# 8iSwitchesOK.net
KiCad netlist of a schematic drawn in EAGLE
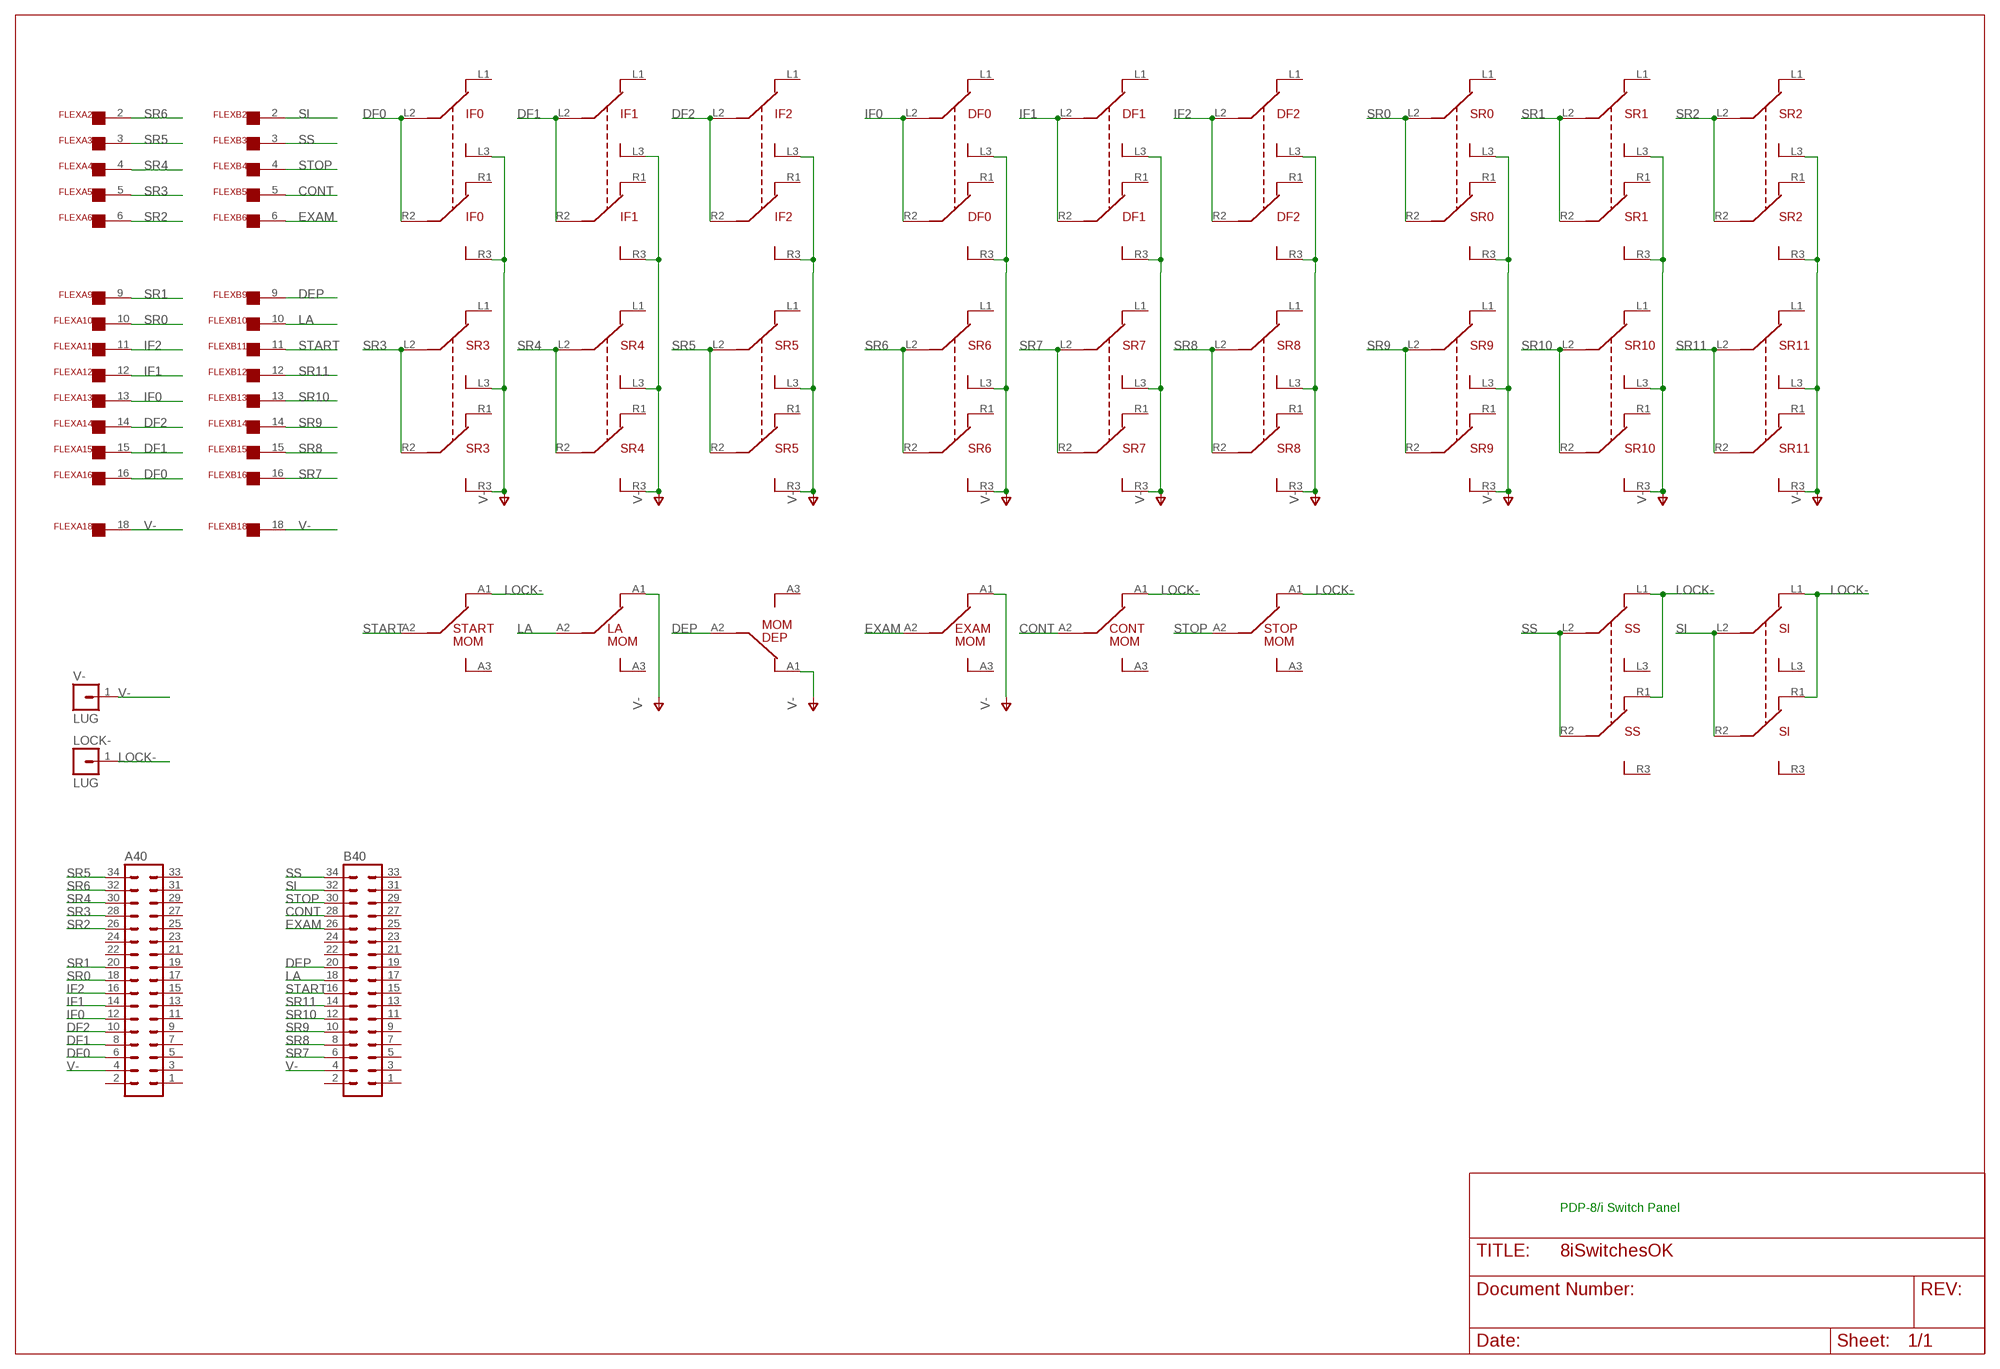
[diagram p0: schematic, sheet 1]

(export (version "E")
  (design (tool "Eeschema 10.0.6"))
  (components
    (comp (ref "A40")
      (value "MA17-2")
      (footprint "eagle-import:MA17-2")
      (libsource (lib "eagle-import") (part "MA17-2"))
    )
    (comp (ref "B40")
      (value "MA17-2")
      (footprint "eagle-import:MA17-2")
      (libsource (lib "eagle-import") (part "MA17-2"))
    )
    (comp (ref "CONT")
      (value "SPDT8I")
      (footprint "eagle-import:SPDT8I")
      (libsource (lib "eagle-import") (part "SPDT8I"))
    )
    (comp (ref "DEP")
      (value "SPDT8I")
      (footprint "eagle-import:SPDT8I")
      (libsource (lib "eagle-import") (part "SPDT8I"))
    )
    (comp (ref "DF0")
      (value "DPDT8I")
      (footprint "eagle-import:DPDT8I")
      (libsource (lib "eagle-import") (part "DPDT8I"))
    )
    (comp (ref "DF1")
      (value "DPDT8I")
      (footprint "eagle-import:DPDT8I")
      (libsource (lib "eagle-import") (part "DPDT8I"))
    )
    (comp (ref "DF2")
      (value "DPDT8I")
      (footprint "eagle-import:DPDT8I")
      (libsource (lib "eagle-import") (part "DPDT8I"))
    )
    (comp (ref "EXAM")
      (value "SPDT8I")
      (footprint "eagle-import:SPDT8I")
      (libsource (lib "eagle-import") (part "SPDT8I"))
    )
    (comp (ref "FLEXA")
      (value "FLEX19")
      (footprint "eagle-import:FLEX19")
      (libsource (lib "eagle-import") (part "FLEX19"))
    )
    (comp (ref "FLEXB")
      (value "FLEX19")
      (footprint "eagle-import:FLEX19")
      (libsource (lib "eagle-import") (part "FLEX19"))
    )
    (comp (ref "IF0")
      (value "DPDT8I")
      (footprint "eagle-import:DPDT8I")
      (libsource (lib "eagle-import") (part "DPDT8I"))
    )
    (comp (ref "IF1")
      (value "DPDT8I")
      (footprint "eagle-import:DPDT8I")
      (libsource (lib "eagle-import") (part "DPDT8I"))
    )
    (comp (ref "IF2")
      (value "DPDT8I")
      (footprint "eagle-import:DPDT8I")
      (libsource (lib "eagle-import") (part "DPDT8I"))
    )
    (comp (ref "LA")
      (value "SPDT8I")
      (footprint "eagle-import:SPDT8I")
      (libsource (lib "eagle-import") (part "SPDT8I"))
    )
    (comp (ref "LOCK-")
      (value "LUG")
      (footprint "eagle-import:SPADELUG")
      (libsource (lib "eagle-import") (part "LUG"))
    )
    (comp (ref "SI")
      (value "DPDT8I")
      (footprint "eagle-import:DPDT8I")
      (libsource (lib "eagle-import") (part "DPDT8I"))
    )
    (comp (ref "SR0")
      (value "DPDT8I")
      (footprint "eagle-import:DPDT8I")
      (libsource (lib "eagle-import") (part "DPDT8I"))
    )
    (comp (ref "SR1")
      (value "DPDT8I")
      (footprint "eagle-import:DPDT8I")
      (libsource (lib "eagle-import") (part "DPDT8I"))
    )
    (comp (ref "SR2")
      (value "DPDT8I")
      (footprint "eagle-import:DPDT8I")
      (libsource (lib "eagle-import") (part "DPDT8I"))
    )
    (comp (ref "SR3")
      (value "DPDT8I")
      (footprint "eagle-import:DPDT8I")
      (libsource (lib "eagle-import") (part "DPDT8I"))
    )
    (comp (ref "SR4")
      (value "DPDT8I")
      (footprint "eagle-import:DPDT8I")
      (libsource (lib "eagle-import") (part "DPDT8I"))
    )
    (comp (ref "SR5")
      (value "DPDT8I")
      (footprint "eagle-import:DPDT8I")
      (libsource (lib "eagle-import") (part "DPDT8I"))
    )
    (comp (ref "SR6")
      (value "DPDT8I")
      (footprint "eagle-import:DPDT8I")
      (libsource (lib "eagle-import") (part "DPDT8I"))
    )
    (comp (ref "SR7")
      (value "DPDT8I")
      (footprint "eagle-import:DPDT8I")
      (libsource (lib "eagle-import") (part "DPDT8I"))
    )
    (comp (ref "SR8")
      (value "DPDT8I")
      (footprint "eagle-import:DPDT8I")
      (libsource (lib "eagle-import") (part "DPDT8I"))
    )
    (comp (ref "SR9")
      (value "DPDT8I")
      (footprint "eagle-import:DPDT8I")
      (libsource (lib "eagle-import") (part "DPDT8I"))
    )
    (comp (ref "SR10")
      (value "DPDT8I")
      (footprint "eagle-import:DPDT8I")
      (libsource (lib "eagle-import") (part "DPDT8I"))
    )
    (comp (ref "SR11")
      (value "DPDT8I")
      (footprint "eagle-import:DPDT8I")
      (libsource (lib "eagle-import") (part "DPDT8I"))
    )
    (comp (ref "SS")
      (value "DPDT8I")
      (footprint "eagle-import:DPDT8I")
      (libsource (lib "eagle-import") (part "DPDT8I"))
    )
    (comp (ref "START")
      (value "SPDT8I")
      (footprint "eagle-import:SPDT8I")
      (libsource (lib "eagle-import") (part "SPDT8I"))
    )
    (comp (ref "STOP")
      (value "SPDT8I")
      (footprint "eagle-import:SPDT8I")
      (libsource (lib "eagle-import") (part "SPDT8I"))
    )
    (comp (ref "V-")
      (value "LUG")
      (footprint "eagle-import:SPADELUG")
      (libsource (lib "eagle-import") (part "LUG"))
    )
  )
  (nets
    (net (code "1") (name "/CONT") (class "Default")
      (node (ref "B40") (pin "28") (pinfunction "28_28") (pintype "passive"))
      (node (ref "CONT") (pin "A2") (pinfunction "A2_A2") (pintype "bidirectional"))
      (node (ref "FLEXB") (pin "5") (pinfunction "1_5") (pintype "passive"))
    )
    (net (code "2") (name "/DEP") (class "Default")
      (node (ref "B40") (pin "20") (pinfunction "20_20") (pintype "passive"))
      (node (ref "DEP") (pin "A2") (pinfunction "A2_A2") (pintype "bidirectional"))
      (node (ref "FLEXB") (pin "9") (pinfunction "1_9") (pintype "passive"))
    )
    (net (code "3") (name "/DF0") (class "Default")
      (node (ref "A40") (pin "6") (pinfunction "6_6") (pintype "passive"))
      (node (ref "FLEXA") (pin "16") (pinfunction "1_16") (pintype "passive"))
      (node (ref "IF0") (pin "L2") (pinfunction "A2_L2") (pintype "bidirectional"))
      (node (ref "IF0") (pin "R2") (pinfunction "B2_R2") (pintype "bidirectional"))
    )
    (net (code "4") (name "/DF1") (class "Default")
      (node (ref "A40") (pin "8") (pinfunction "8_8") (pintype "passive"))
      (node (ref "FLEXA") (pin "15") (pinfunction "1_15") (pintype "passive"))
      (node (ref "IF1") (pin "L2") (pinfunction "A2_L2") (pintype "bidirectional"))
      (node (ref "IF1") (pin "R2") (pinfunction "B2_R2") (pintype "bidirectional"))
    )
    (net (code "5") (name "/DF2") (class "Default")
      (node (ref "A40") (pin "10") (pinfunction "10_10") (pintype "passive"))
      (node (ref "FLEXA") (pin "14") (pinfunction "1_14") (pintype "passive"))
      (node (ref "IF2") (pin "L2") (pinfunction "A2_L2") (pintype "bidirectional"))
      (node (ref "IF2") (pin "R2") (pinfunction "B2_R2") (pintype "bidirectional"))
    )
    (net (code "6") (name "/EXAM") (class "Default")
      (node (ref "B40") (pin "26") (pinfunction "26_26") (pintype "passive"))
      (node (ref "EXAM") (pin "A2") (pinfunction "A2_A2") (pintype "bidirectional"))
      (node (ref "FLEXB") (pin "6") (pinfunction "1_6") (pintype "passive"))
    )
    (net (code "7") (name "/IF0") (class "Default")
      (node (ref "A40") (pin "12") (pinfunction "12_12") (pintype "passive"))
      (node (ref "DF0") (pin "L2") (pinfunction "A2_L2") (pintype "bidirectional"))
      (node (ref "DF0") (pin "R2") (pinfunction "B2_R2") (pintype "bidirectional"))
      (node (ref "FLEXA") (pin "13") (pinfunction "1_13") (pintype "passive"))
    )
    (net (code "8") (name "/IF1") (class "Default")
      (node (ref "A40") (pin "14") (pinfunction "14_14") (pintype "passive"))
      (node (ref "DF1") (pin "L2") (pinfunction "A2_L2") (pintype "bidirectional"))
      (node (ref "DF1") (pin "R2") (pinfunction "B2_R2") (pintype "bidirectional"))
      (node (ref "FLEXA") (pin "12") (pinfunction "1_12") (pintype "passive"))
    )
    (net (code "9") (name "/IF2") (class "Default")
      (node (ref "A40") (pin "16") (pinfunction "16_16") (pintype "passive"))
      (node (ref "DF2") (pin "L2") (pinfunction "A2_L2") (pintype "bidirectional"))
      (node (ref "DF2") (pin "R2") (pinfunction "B2_R2") (pintype "bidirectional"))
      (node (ref "FLEXA") (pin "11") (pinfunction "1_11") (pintype "passive"))
    )
    (net (code "10") (name "/LA") (class "Default")
      (node (ref "B40") (pin "18") (pinfunction "18_18") (pintype "passive"))
      (node (ref "FLEXB") (pin "10") (pinfunction "1_10") (pintype "passive"))
      (node (ref "LA") (pin "A2") (pinfunction "A2_A2") (pintype "bidirectional"))
    )
    (net (code "11") (name "/LOCK-") (class "Default")
      (node (ref "CONT") (pin "A1") (pinfunction "A1_A1") (pintype "bidirectional"))
      (node (ref "LOCK-") (pin "1") (pinfunction "1_1") (pintype "passive"))
      (node (ref "SI") (pin "L1") (pinfunction "A1_L1") (pintype "bidirectional"))
      (node (ref "SI") (pin "R1") (pinfunction "B1_R1") (pintype "bidirectional"))
      (node (ref "SS") (pin "L1") (pinfunction "A1_L1") (pintype "bidirectional"))
      (node (ref "SS") (pin "R1") (pinfunction "B1_R1") (pintype "bidirectional"))
      (node (ref "START") (pin "A1") (pinfunction "A1_A1") (pintype "bidirectional"))
      (node (ref "STOP") (pin "A1") (pinfunction "A1_A1") (pintype "bidirectional"))
    )
    (net (code "12") (name "/SI") (class "Default")
      (node (ref "B40") (pin "32") (pinfunction "32_32") (pintype "passive"))
      (node (ref "FLEXB") (pin "2") (pinfunction "1_2") (pintype "passive"))
      (node (ref "SI") (pin "L2") (pinfunction "A2_L2") (pintype "bidirectional"))
      (node (ref "SI") (pin "R2") (pinfunction "B2_R2") (pintype "bidirectional"))
    )
    (net (code "13") (name "/SR0") (class "Default")
      (node (ref "A40") (pin "18") (pinfunction "18_18") (pintype "passive"))
      (node (ref "FLEXA") (pin "10") (pinfunction "1_10") (pintype "passive"))
      (node (ref "SR0") (pin "L2") (pinfunction "A2_L2") (pintype "bidirectional"))
      (node (ref "SR0") (pin "R2") (pinfunction "B2_R2") (pintype "bidirectional"))
    )
    (net (code "14") (name "/SR1") (class "Default")
      (node (ref "A40") (pin "20") (pinfunction "20_20") (pintype "passive"))
      (node (ref "FLEXA") (pin "9") (pinfunction "1_9") (pintype "passive"))
      (node (ref "SR1") (pin "L2") (pinfunction "A2_L2") (pintype "bidirectional"))
      (node (ref "SR1") (pin "R2") (pinfunction "B2_R2") (pintype "bidirectional"))
    )
    (net (code "15") (name "/SR2") (class "Default")
      (node (ref "A40") (pin "26") (pinfunction "26_26") (pintype "passive"))
      (node (ref "FLEXA") (pin "6") (pinfunction "1_6") (pintype "passive"))
      (node (ref "SR2") (pin "L2") (pinfunction "A2_L2") (pintype "bidirectional"))
      (node (ref "SR2") (pin "R2") (pinfunction "B2_R2") (pintype "bidirectional"))
    )
    (net (code "16") (name "/SR3") (class "Default")
      (node (ref "A40") (pin "28") (pinfunction "28_28") (pintype "passive"))
      (node (ref "FLEXA") (pin "5") (pinfunction "1_5") (pintype "passive"))
      (node (ref "SR3") (pin "L2") (pinfunction "A2_L2") (pintype "bidirectional"))
      (node (ref "SR3") (pin "R2") (pinfunction "B2_R2") (pintype "bidirectional"))
    )
    (net (code "17") (name "/SR4") (class "Default")
      (node (ref "A40") (pin "30") (pinfunction "30_30") (pintype "passive"))
      (node (ref "FLEXA") (pin "4") (pinfunction "1_4") (pintype "passive"))
      (node (ref "SR4") (pin "L2") (pinfunction "A2_L2") (pintype "bidirectional"))
      (node (ref "SR4") (pin "R2") (pinfunction "B2_R2") (pintype "bidirectional"))
    )
    (net (code "18") (name "/SR5") (class "Default")
      (node (ref "A40") (pin "34") (pinfunction "34_34") (pintype "passive"))
      (node (ref "FLEXA") (pin "3") (pinfunction "1_3") (pintype "passive"))
      (node (ref "SR5") (pin "L2") (pinfunction "A2_L2") (pintype "bidirectional"))
      (node (ref "SR5") (pin "R2") (pinfunction "B2_R2") (pintype "bidirectional"))
    )
    (net (code "19") (name "/SR6") (class "Default")
      (node (ref "A40") (pin "32") (pinfunction "32_32") (pintype "passive"))
      (node (ref "FLEXA") (pin "2") (pinfunction "1_2") (pintype "passive"))
      (node (ref "SR6") (pin "L2") (pinfunction "A2_L2") (pintype "bidirectional"))
      (node (ref "SR6") (pin "R2") (pinfunction "B2_R2") (pintype "bidirectional"))
    )
    (net (code "20") (name "/SR7") (class "Default")
      (node (ref "B40") (pin "6") (pinfunction "6_6") (pintype "passive"))
      (node (ref "FLEXB") (pin "16") (pinfunction "1_16") (pintype "passive"))
      (node (ref "SR7") (pin "L2") (pinfunction "A2_L2") (pintype "bidirectional"))
      (node (ref "SR7") (pin "R2") (pinfunction "B2_R2") (pintype "bidirectional"))
    )
    (net (code "21") (name "/SR8") (class "Default")
      (node (ref "B40") (pin "8") (pinfunction "8_8") (pintype "passive"))
      (node (ref "FLEXB") (pin "15") (pinfunction "1_15") (pintype "passive"))
      (node (ref "SR8") (pin "L2") (pinfunction "A2_L2") (pintype "bidirectional"))
      (node (ref "SR8") (pin "R2") (pinfunction "B2_R2") (pintype "bidirectional"))
    )
    (net (code "22") (name "/SR9") (class "Default")
      (node (ref "B40") (pin "10") (pinfunction "10_10") (pintype "passive"))
      (node (ref "FLEXB") (pin "14") (pinfunction "1_14") (pintype "passive"))
      (node (ref "SR9") (pin "L2") (pinfunction "A2_L2") (pintype "bidirectional"))
      (node (ref "SR9") (pin "R2") (pinfunction "B2_R2") (pintype "bidirectional"))
    )
    (net (code "23") (name "/SR10") (class "Default")
      (node (ref "B40") (pin "12") (pinfunction "12_12") (pintype "passive"))
      (node (ref "FLEXB") (pin "13") (pinfunction "1_13") (pintype "passive"))
      (node (ref "SR10") (pin "L2") (pinfunction "A2_L2") (pintype "bidirectional"))
      (node (ref "SR10") (pin "R2") (pinfunction "B2_R2") (pintype "bidirectional"))
    )
    (net (code "24") (name "/SR11") (class "Default")
      (node (ref "B40") (pin "14") (pinfunction "14_14") (pintype "passive"))
      (node (ref "FLEXB") (pin "12") (pinfunction "1_12") (pintype "passive"))
      (node (ref "SR11") (pin "L2") (pinfunction "A2_L2") (pintype "bidirectional"))
      (node (ref "SR11") (pin "R2") (pinfunction "B2_R2") (pintype "bidirectional"))
    )
    (net (code "25") (name "/SS") (class "Default")
      (node (ref "B40") (pin "34") (pinfunction "34_34") (pintype "passive"))
      (node (ref "FLEXB") (pin "3") (pinfunction "1_3") (pintype "passive"))
      (node (ref "SS") (pin "L2") (pinfunction "A2_L2") (pintype "bidirectional"))
      (node (ref "SS") (pin "R2") (pinfunction "B2_R2") (pintype "bidirectional"))
    )
    (net (code "26") (name "/START") (class "Default")
      (node (ref "B40") (pin "16") (pinfunction "16_16") (pintype "passive"))
      (node (ref "FLEXB") (pin "11") (pinfunction "1_11") (pintype "passive"))
      (node (ref "START") (pin "A2") (pinfunction "A2_A2") (pintype "bidirectional"))
    )
    (net (code "27") (name "/STOP") (class "Default")
      (node (ref "B40") (pin "30") (pinfunction "30_30") (pintype "passive"))
      (node (ref "FLEXB") (pin "4") (pinfunction "1_4") (pintype "passive"))
      (node (ref "STOP") (pin "A2") (pinfunction "A2_A2") (pintype "bidirectional"))
    )
    (net (code "28") (name "V-") (class "Default")
      (node (ref "A40") (pin "4") (pinfunction "4_4") (pintype "passive"))
      (node (ref "B40") (pin "4") (pinfunction "4_4") (pintype "passive"))
      (node (ref "DEP") (pin "A1") (pinfunction "A1_A1") (pintype "bidirectional"))
      (node (ref "DF0") (pin "L3") (pinfunction "A3_L3") (pintype "bidirectional"))
      (node (ref "DF0") (pin "R3") (pinfunction "B3_R3") (pintype "bidirectional"))
      (node (ref "DF1") (pin "L3") (pinfunction "A3_L3") (pintype "bidirectional"))
      (node (ref "DF1") (pin "R3") (pinfunction "B3_R3") (pintype "bidirectional"))
      (node (ref "DF2") (pin "L3") (pinfunction "A3_L3") (pintype "bidirectional"))
      (node (ref "DF2") (pin "R3") (pinfunction "B3_R3") (pintype "bidirectional"))
      (node (ref "EXAM") (pin "A1") (pinfunction "A1_A1") (pintype "bidirectional"))
      (node (ref "FLEXA") (pin "18") (pinfunction "1_18") (pintype "passive"))
      (node (ref "FLEXB") (pin "18") (pinfunction "1_18") (pintype "passive"))
      (node (ref "IF0") (pin "L3") (pinfunction "A3_L3") (pintype "bidirectional"))
      (node (ref "IF0") (pin "R3") (pinfunction "B3_R3") (pintype "bidirectional"))
      (node (ref "IF1") (pin "L3") (pinfunction "A3_L3") (pintype "bidirectional"))
      (node (ref "IF1") (pin "R3") (pinfunction "B3_R3") (pintype "bidirectional"))
      (node (ref "IF2") (pin "L3") (pinfunction "A3_L3") (pintype "bidirectional"))
      (node (ref "IF2") (pin "R3") (pinfunction "B3_R3") (pintype "bidirectional"))
      (node (ref "LA") (pin "A1") (pinfunction "A1_A1") (pintype "bidirectional"))
      (node (ref "SR0") (pin "L3") (pinfunction "A3_L3") (pintype "bidirectional"))
      (node (ref "SR0") (pin "R3") (pinfunction "B3_R3") (pintype "bidirectional"))
      (node (ref "SR1") (pin "L3") (pinfunction "A3_L3") (pintype "bidirectional"))
      (node (ref "SR1") (pin "R3") (pinfunction "B3_R3") (pintype "bidirectional"))
      (node (ref "SR10") (pin "L3") (pinfunction "A3_L3") (pintype "bidirectional"))
      (node (ref "SR10") (pin "R3") (pinfunction "B3_R3") (pintype "bidirectional"))
      (node (ref "SR11") (pin "L3") (pinfunction "A3_L3") (pintype "bidirectional"))
      (node (ref "SR11") (pin "R3") (pinfunction "B3_R3") (pintype "bidirectional"))
      (node (ref "SR2") (pin "L3") (pinfunction "A3_L3") (pintype "bidirectional"))
      (node (ref "SR2") (pin "R3") (pinfunction "B3_R3") (pintype "bidirectional"))
      (node (ref "SR3") (pin "L3") (pinfunction "A3_L3") (pintype "bidirectional"))
      (node (ref "SR3") (pin "R3") (pinfunction "B3_R3") (pintype "bidirectional"))
      (node (ref "SR4") (pin "L3") (pinfunction "A3_L3") (pintype "bidirectional"))
      (node (ref "SR4") (pin "R3") (pinfunction "B3_R3") (pintype "bidirectional"))
      (node (ref "SR5") (pin "L3") (pinfunction "A3_L3") (pintype "bidirectional"))
      (node (ref "SR5") (pin "R3") (pinfunction "B3_R3") (pintype "bidirectional"))
      (node (ref "SR6") (pin "L3") (pinfunction "A3_L3") (pintype "bidirectional"))
      (node (ref "SR6") (pin "R3") (pinfunction "B3_R3") (pintype "bidirectional"))
      (node (ref "SR7") (pin "L3") (pinfunction "A3_L3") (pintype "bidirectional"))
      (node (ref "SR7") (pin "R3") (pinfunction "B3_R3") (pintype "bidirectional"))
      (node (ref "SR8") (pin "L3") (pinfunction "A3_L3") (pintype "bidirectional"))
      (node (ref "SR8") (pin "R3") (pinfunction "B3_R3") (pintype "bidirectional"))
      (node (ref "SR9") (pin "L3") (pinfunction "A3_L3") (pintype "bidirectional"))
      (node (ref "SR9") (pin "R3") (pinfunction "B3_R3") (pintype "bidirectional"))
      (node (ref "V-") (pin "1") (pinfunction "1_1") (pintype "passive"))
    )
    (net (code "29") (name "unconnected-(A40-Pad1)") (class "Default")
      (node (ref "A40") (pin "1") (pinfunction "1_1") (pintype "passive"))
    )
    (net (code "30") (name "unconnected-(A40-Pad2)") (class "Default")
      (node (ref "A40") (pin "2") (pinfunction "2_2") (pintype "passive"))
    )
    (net (code "31") (name "unconnected-(A40-Pad3)") (class "Default")
      (node (ref "A40") (pin "3") (pinfunction "3_3") (pintype "passive"))
    )
    (net (code "32") (name "unconnected-(A40-Pad5)") (class "Default")
      (node (ref "A40") (pin "5") (pinfunction "5_5") (pintype "passive"))
    )
    (net (code "33") (name "unconnected-(A40-Pad7)") (class "Default")
      (node (ref "A40") (pin "7") (pinfunction "7_7") (pintype "passive"))
    )
    (net (code "34") (name "unconnected-(A40-Pad9)") (class "Default")
      (node (ref "A40") (pin "9") (pinfunction "9_9") (pintype "passive"))
    )
    (net (code "35") (name "unconnected-(A40-Pad11)") (class "Default")
      (node (ref "A40") (pin "11") (pinfunction "11_11") (pintype "passive"))
    )
    (net (code "36") (name "unconnected-(A40-Pad13)") (class "Default")
      (node (ref "A40") (pin "13") (pinfunction "13_13") (pintype "passive"))
    )
    (net (code "37") (name "unconnected-(A40-Pad15)") (class "Default")
      (node (ref "A40") (pin "15") (pinfunction "15_15") (pintype "passive"))
    )
    (net (code "38") (name "unconnected-(A40-Pad17)") (class "Default")
      (node (ref "A40") (pin "17") (pinfunction "17_17") (pintype "passive"))
    )
    (net (code "39") (name "unconnected-(A40-Pad19)") (class "Default")
      (node (ref "A40") (pin "19") (pinfunction "19_19") (pintype "passive"))
    )
    (net (code "40") (name "unconnected-(A40-Pad21)") (class "Default")
      (node (ref "A40") (pin "21") (pinfunction "21_21") (pintype "passive"))
    )
    (net (code "41") (name "unconnected-(A40-Pad22)") (class "Default")
      (node (ref "A40") (pin "22") (pinfunction "22_22") (pintype "passive"))
    )
    (net (code "42") (name "unconnected-(A40-Pad23)") (class "Default")
      (node (ref "A40") (pin "23") (pinfunction "23_23") (pintype "passive"))
    )
    (net (code "43") (name "unconnected-(A40-Pad24)") (class "Default")
      (node (ref "A40") (pin "24") (pinfunction "24_24") (pintype "passive"))
    )
    (net (code "44") (name "unconnected-(A40-Pad25)") (class "Default")
      (node (ref "A40") (pin "25") (pinfunction "25_25") (pintype "passive"))
    )
    (net (code "45") (name "unconnected-(A40-Pad27)") (class "Default")
      (node (ref "A40") (pin "27") (pinfunction "27_27") (pintype "passive"))
    )
    (net (code "46") (name "unconnected-(A40-Pad29)") (class "Default")
      (node (ref "A40") (pin "29") (pinfunction "29_29") (pintype "passive"))
    )
    (net (code "47") (name "unconnected-(A40-Pad31)") (class "Default")
      (node (ref "A40") (pin "31") (pinfunction "31_31") (pintype "passive"))
    )
    (net (code "48") (name "unconnected-(A40-Pad33)") (class "Default")
      (node (ref "A40") (pin "33") (pinfunction "33_33") (pintype "passive"))
    )
    (net (code "49") (name "unconnected-(B40-Pad1)") (class "Default")
      (node (ref "B40") (pin "1") (pinfunction "1_1") (pintype "passive"))
    )
    (net (code "50") (name "unconnected-(B40-Pad2)") (class "Default")
      (node (ref "B40") (pin "2") (pinfunction "2_2") (pintype "passive"))
    )
    (net (code "51") (name "unconnected-(B40-Pad3)") (class "Default")
      (node (ref "B40") (pin "3") (pinfunction "3_3") (pintype "passive"))
    )
    (net (code "52") (name "unconnected-(B40-Pad5)") (class "Default")
      (node (ref "B40") (pin "5") (pinfunction "5_5") (pintype "passive"))
    )
    (net (code "53") (name "unconnected-(B40-Pad7)") (class "Default")
      (node (ref "B40") (pin "7") (pinfunction "7_7") (pintype "passive"))
    )
    (net (code "54") (name "unconnected-(B40-Pad9)") (class "Default")
      (node (ref "B40") (pin "9") (pinfunction "9_9") (pintype "passive"))
    )
    (net (code "55") (name "unconnected-(B40-Pad11)") (class "Default")
      (node (ref "B40") (pin "11") (pinfunction "11_11") (pintype "passive"))
    )
    (net (code "56") (name "unconnected-(B40-Pad13)") (class "Default")
      (node (ref "B40") (pin "13") (pinfunction "13_13") (pintype "passive"))
    )
    (net (code "57") (name "unconnected-(B40-Pad15)") (class "Default")
      (node (ref "B40") (pin "15") (pinfunction "15_15") (pintype "passive"))
    )
    (net (code "58") (name "unconnected-(B40-Pad17)") (class "Default")
      (node (ref "B40") (pin "17") (pinfunction "17_17") (pintype "passive"))
    )
    (net (code "59") (name "unconnected-(B40-Pad19)") (class "Default")
      (node (ref "B40") (pin "19") (pinfunction "19_19") (pintype "passive"))
    )
    (net (code "60") (name "unconnected-(B40-Pad21)") (class "Default")
      (node (ref "B40") (pin "21") (pinfunction "21_21") (pintype "passive"))
    )
    (net (code "61") (name "unconnected-(B40-Pad22)") (class "Default")
      (node (ref "B40") (pin "22") (pinfunction "22_22") (pintype "passive"))
    )
    (net (code "62") (name "unconnected-(B40-Pad23)") (class "Default")
      (node (ref "B40") (pin "23") (pinfunction "23_23") (pintype "passive"))
    )
    (net (code "63") (name "unconnected-(B40-Pad24)") (class "Default")
      (node (ref "B40") (pin "24") (pinfunction "24_24") (pintype "passive"))
    )
    (net (code "64") (name "unconnected-(B40-Pad25)") (class "Default")
      (node (ref "B40") (pin "25") (pinfunction "25_25") (pintype "passive"))
    )
    (net (code "65") (name "unconnected-(B40-Pad27)") (class "Default")
      (node (ref "B40") (pin "27") (pinfunction "27_27") (pintype "passive"))
    )
    (net (code "66") (name "unconnected-(B40-Pad29)") (class "Default")
      (node (ref "B40") (pin "29") (pinfunction "29_29") (pintype "passive"))
    )
    (net (code "67") (name "unconnected-(B40-Pad31)") (class "Default")
      (node (ref "B40") (pin "31") (pinfunction "31_31") (pintype "passive"))
    )
    (net (code "68") (name "unconnected-(B40-Pad33)") (class "Default")
      (node (ref "B40") (pin "33") (pinfunction "33_33") (pintype "passive"))
    )
    (net (code "69") (name "unconnected-(CONT-PadA3)") (class "Default")
      (node (ref "CONT") (pin "A3") (pinfunction "A3_A3") (pintype "bidirectional"))
    )
    (net (code "70") (name "unconnected-(DEP-PadA3)") (class "Default")
      (node (ref "DEP") (pin "A3") (pinfunction "A3_A3") (pintype "bidirectional"))
    )
    (net (code "71") (name "unconnected-(DF0-A1-PadL1)") (class "Default")
      (node (ref "DF0") (pin "L1") (pinfunction "A1_L1") (pintype "bidirectional"))
    )
    (net (code "72") (name "unconnected-(DF0-B1-PadR1)") (class "Default")
      (node (ref "DF0") (pin "R1") (pinfunction "B1_R1") (pintype "bidirectional"))
    )
    (net (code "73") (name "unconnected-(DF1-A1-PadL1)") (class "Default")
      (node (ref "DF1") (pin "L1") (pinfunction "A1_L1") (pintype "bidirectional"))
    )
    (net (code "74") (name "unconnected-(DF1-B1-PadR1)") (class "Default")
      (node (ref "DF1") (pin "R1") (pinfunction "B1_R1") (pintype "bidirectional"))
    )
    (net (code "75") (name "unconnected-(DF2-A1-PadL1)") (class "Default")
      (node (ref "DF2") (pin "L1") (pinfunction "A1_L1") (pintype "bidirectional"))
    )
    (net (code "76") (name "unconnected-(DF2-B1-PadR1)") (class "Default")
      (node (ref "DF2") (pin "R1") (pinfunction "B1_R1") (pintype "bidirectional"))
    )
    (net (code "77") (name "unconnected-(EXAM-PadA3)") (class "Default")
      (node (ref "EXAM") (pin "A3") (pinfunction "A3_A3") (pintype "bidirectional"))
    )
    (net (code "78") (name "unconnected-(IF0-A1-PadL1)") (class "Default")
      (node (ref "IF0") (pin "L1") (pinfunction "A1_L1") (pintype "bidirectional"))
    )
    (net (code "79") (name "unconnected-(IF0-B1-PadR1)") (class "Default")
      (node (ref "IF0") (pin "R1") (pinfunction "B1_R1") (pintype "bidirectional"))
    )
    (net (code "80") (name "unconnected-(IF1-A1-PadL1)") (class "Default")
      (node (ref "IF1") (pin "L1") (pinfunction "A1_L1") (pintype "bidirectional"))
    )
    (net (code "81") (name "unconnected-(IF1-B1-PadR1)") (class "Default")
      (node (ref "IF1") (pin "R1") (pinfunction "B1_R1") (pintype "bidirectional"))
    )
    (net (code "82") (name "unconnected-(IF2-A1-PadL1)") (class "Default")
      (node (ref "IF2") (pin "L1") (pinfunction "A1_L1") (pintype "bidirectional"))
    )
    (net (code "83") (name "unconnected-(IF2-B1-PadR1)") (class "Default")
      (node (ref "IF2") (pin "R1") (pinfunction "B1_R1") (pintype "bidirectional"))
    )
    (net (code "84") (name "unconnected-(LA-PadA3)") (class "Default")
      (node (ref "LA") (pin "A3") (pinfunction "A3_A3") (pintype "bidirectional"))
    )
    (net (code "85") (name "unconnected-(SI-A3-PadL3)") (class "Default")
      (node (ref "SI") (pin "L3") (pinfunction "A3_L3") (pintype "bidirectional"))
    )
    (net (code "86") (name "unconnected-(SI-B3-PadR3)") (class "Default")
      (node (ref "SI") (pin "R3") (pinfunction "B3_R3") (pintype "bidirectional"))
    )
    (net (code "87") (name "unconnected-(SR0-A1-PadL1)") (class "Default")
      (node (ref "SR0") (pin "L1") (pinfunction "A1_L1") (pintype "bidirectional"))
    )
    (net (code "88") (name "unconnected-(SR0-B1-PadR1)") (class "Default")
      (node (ref "SR0") (pin "R1") (pinfunction "B1_R1") (pintype "bidirectional"))
    )
    (net (code "89") (name "unconnected-(SR1-A1-PadL1)") (class "Default")
      (node (ref "SR1") (pin "L1") (pinfunction "A1_L1") (pintype "bidirectional"))
    )
    (net (code "90") (name "unconnected-(SR1-B1-PadR1)") (class "Default")
      (node (ref "SR1") (pin "R1") (pinfunction "B1_R1") (pintype "bidirectional"))
    )
    (net (code "91") (name "unconnected-(SR2-A1-PadL1)") (class "Default")
      (node (ref "SR2") (pin "L1") (pinfunction "A1_L1") (pintype "bidirectional"))
    )
    (net (code "92") (name "unconnected-(SR2-B1-PadR1)") (class "Default")
      (node (ref "SR2") (pin "R1") (pinfunction "B1_R1") (pintype "bidirectional"))
    )
    (net (code "93") (name "unconnected-(SR3-A1-PadL1)") (class "Default")
      (node (ref "SR3") (pin "L1") (pinfunction "A1_L1") (pintype "bidirectional"))
    )
    (net (code "94") (name "unconnected-(SR3-B1-PadR1)") (class "Default")
      (node (ref "SR3") (pin "R1") (pinfunction "B1_R1") (pintype "bidirectional"))
    )
    (net (code "95") (name "unconnected-(SR4-A1-PadL1)") (class "Default")
      (node (ref "SR4") (pin "L1") (pinfunction "A1_L1") (pintype "bidirectional"))
    )
    (net (code "96") (name "unconnected-(SR4-B1-PadR1)") (class "Default")
      (node (ref "SR4") (pin "R1") (pinfunction "B1_R1") (pintype "bidirectional"))
    )
    (net (code "97") (name "unconnected-(SR5-A1-PadL1)") (class "Default")
      (node (ref "SR5") (pin "L1") (pinfunction "A1_L1") (pintype "bidirectional"))
    )
    (net (code "98") (name "unconnected-(SR5-B1-PadR1)") (class "Default")
      (node (ref "SR5") (pin "R1") (pinfunction "B1_R1") (pintype "bidirectional"))
    )
    (net (code "99") (name "unconnected-(SR6-A1-PadL1)") (class "Default")
      (node (ref "SR6") (pin "L1") (pinfunction "A1_L1") (pintype "bidirectional"))
    )
    (net (code "100") (name "unconnected-(SR6-B1-PadR1)") (class "Default")
      (node (ref "SR6") (pin "R1") (pinfunction "B1_R1") (pintype "bidirectional"))
    )
    (net (code "101") (name "unconnected-(SR7-A1-PadL1)") (class "Default")
      (node (ref "SR7") (pin "L1") (pinfunction "A1_L1") (pintype "bidirectional"))
    )
    (net (code "102") (name "unconnected-(SR7-B1-PadR1)") (class "Default")
      (node (ref "SR7") (pin "R1") (pinfunction "B1_R1") (pintype "bidirectional"))
    )
    (net (code "103") (name "unconnected-(SR8-A1-PadL1)") (class "Default")
      (node (ref "SR8") (pin "L1") (pinfunction "A1_L1") (pintype "bidirectional"))
    )
    (net (code "104") (name "unconnected-(SR8-B1-PadR1)") (class "Default")
      (node (ref "SR8") (pin "R1") (pinfunction "B1_R1") (pintype "bidirectional"))
    )
    (net (code "105") (name "unconnected-(SR9-A1-PadL1)") (class "Default")
      (node (ref "SR9") (pin "L1") (pinfunction "A1_L1") (pintype "bidirectional"))
    )
    (net (code "106") (name "unconnected-(SR9-B1-PadR1)") (class "Default")
      (node (ref "SR9") (pin "R1") (pinfunction "B1_R1") (pintype "bidirectional"))
    )
    (net (code "107") (name "unconnected-(SR10-A1-PadL1)") (class "Default")
      (node (ref "SR10") (pin "L1") (pinfunction "A1_L1") (pintype "bidirectional"))
    )
    (net (code "108") (name "unconnected-(SR10-B1-PadR1)") (class "Default")
      (node (ref "SR10") (pin "R1") (pinfunction "B1_R1") (pintype "bidirectional"))
    )
    (net (code "109") (name "unconnected-(SR11-A1-PadL1)") (class "Default")
      (node (ref "SR11") (pin "L1") (pinfunction "A1_L1") (pintype "bidirectional"))
    )
    (net (code "110") (name "unconnected-(SR11-B1-PadR1)") (class "Default")
      (node (ref "SR11") (pin "R1") (pinfunction "B1_R1") (pintype "bidirectional"))
    )
    (net (code "111") (name "unconnected-(SS-A3-PadL3)") (class "Default")
      (node (ref "SS") (pin "L3") (pinfunction "A3_L3") (pintype "bidirectional"))
    )
    (net (code "112") (name "unconnected-(SS-B3-PadR3)") (class "Default")
      (node (ref "SS") (pin "R3") (pinfunction "B3_R3") (pintype "bidirectional"))
    )
    (net (code "113") (name "unconnected-(START-PadA3)") (class "Default")
      (node (ref "START") (pin "A3") (pinfunction "A3_A3") (pintype "bidirectional"))
    )
    (net (code "114") (name "unconnected-(STOP-PadA3)") (class "Default")
      (node (ref "STOP") (pin "A3") (pinfunction "A3_A3") (pintype "bidirectional"))
    )
  )
)
